# BME_280_Sheet1.net
KiCad netlist of a schematic drawn in Altium Designer
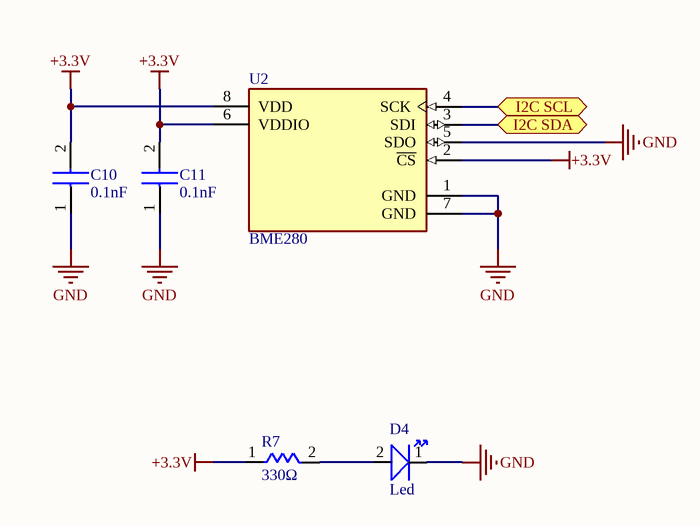
[diagram p0: BME_280_Sheet1.SchDoc]

(export (version "E")
  (design (tool "Eeschema 10.0.6"))
  (components
    (comp (ref "C10")
      (value "0.1nF")
      (footprint "CAP - 0603")
      (description "Capacitor")
      (libsource (lib "Faydali_Yuk_Schlib1") (part "CAP"))
    )
    (comp (ref "C11")
      (value "0.1nF")
      (footprint "CAP - 0603")
      (description "Capacitor")
      (libsource (lib "Faydali_Yuk_Schlib1") (part "CAP"))
    )
    (comp (ref "D4")
      (value "Led")
      (footprint "LED - 0603")
      (description "HL-PST-1608U51GC - LED SMD 0603 GREEN 500mcd 120° WATER CLEAR")
      (libsource (lib "Faydali_Yuk_Schlib1") (part "Led"))
    )
    (comp (ref "R7")
      (value "330Ω")
      (footprint "RES - 0603")
      (description "SMD Res")
      (libsource (lib "Faydali_Yuk_Schlib1") (part "Res"))
    )
    (comp (ref "U2")
      (value "BME280")
      (footprint "BME280 - FP-BME280-MFG")
      (description "SENSOR PRESSURE HUMIDITY TEMP")
      (libsource (lib "Faydali_Yuk_Schlib1") (part "BME 280- CMP-2000-05073-3"))
    )
  )
  (nets
    (net (code "1") (name "+3.3V") (class "Default")
      (node (ref "C10") (pin "2") (pinfunction "2_2") (pintype "passive"))
      (node (ref "C11") (pin "2") (pinfunction "2_2") (pintype "passive"))
      (node (ref "R7") (pin "1") (pinfunction "1_1") (pintype "passive"))
      (node (ref "U2") (pin "2") (pinfunction "~{CS}_2") (pintype "input"))
      (node (ref "U2") (pin "6") (pinfunction "VDDIO_6") (pintype "power_in"))
      (node (ref "U2") (pin "8") (pinfunction "VDD_8") (pintype "power_in"))
    )
    (net (code "2") (name "/I2C SCL") (class "Default")
      (node (ref "U2") (pin "4") (pinfunction "SCK_4") (pintype "input"))
    )
    (net (code "3") (name "/I2C SDA") (class "Default")
      (node (ref "U2") (pin "3") (pinfunction "SDI_3") (pintype "bidirectional"))
    )
    (net (code "4") (name "GND") (class "Default")
      (node (ref "C10") (pin "1") (pinfunction "1_1") (pintype "passive"))
      (node (ref "C11") (pin "1") (pinfunction "1_1") (pintype "passive"))
      (node (ref "D4") (pin "1") (pinfunction "1_1") (pintype "passive"))
      (node (ref "U2") (pin "1") (pinfunction "GND_1") (pintype "power_in"))
      (node (ref "U2") (pin "5") (pinfunction "SDO_5") (pintype "bidirectional"))
      (node (ref "U2") (pin "7") (pinfunction "GND_7") (pintype "power_in"))
    )
    (net (code "5") (name "Net-(D4-Pad2)") (class "Default")
      (node (ref "D4") (pin "2") (pinfunction "2_2") (pintype "passive"))
      (node (ref "R7") (pin "2") (pinfunction "2_2") (pintype "passive"))
    )
  )
)
